# XmasTree.net
KiCad netlist of a schematic drawn in Altium Designer
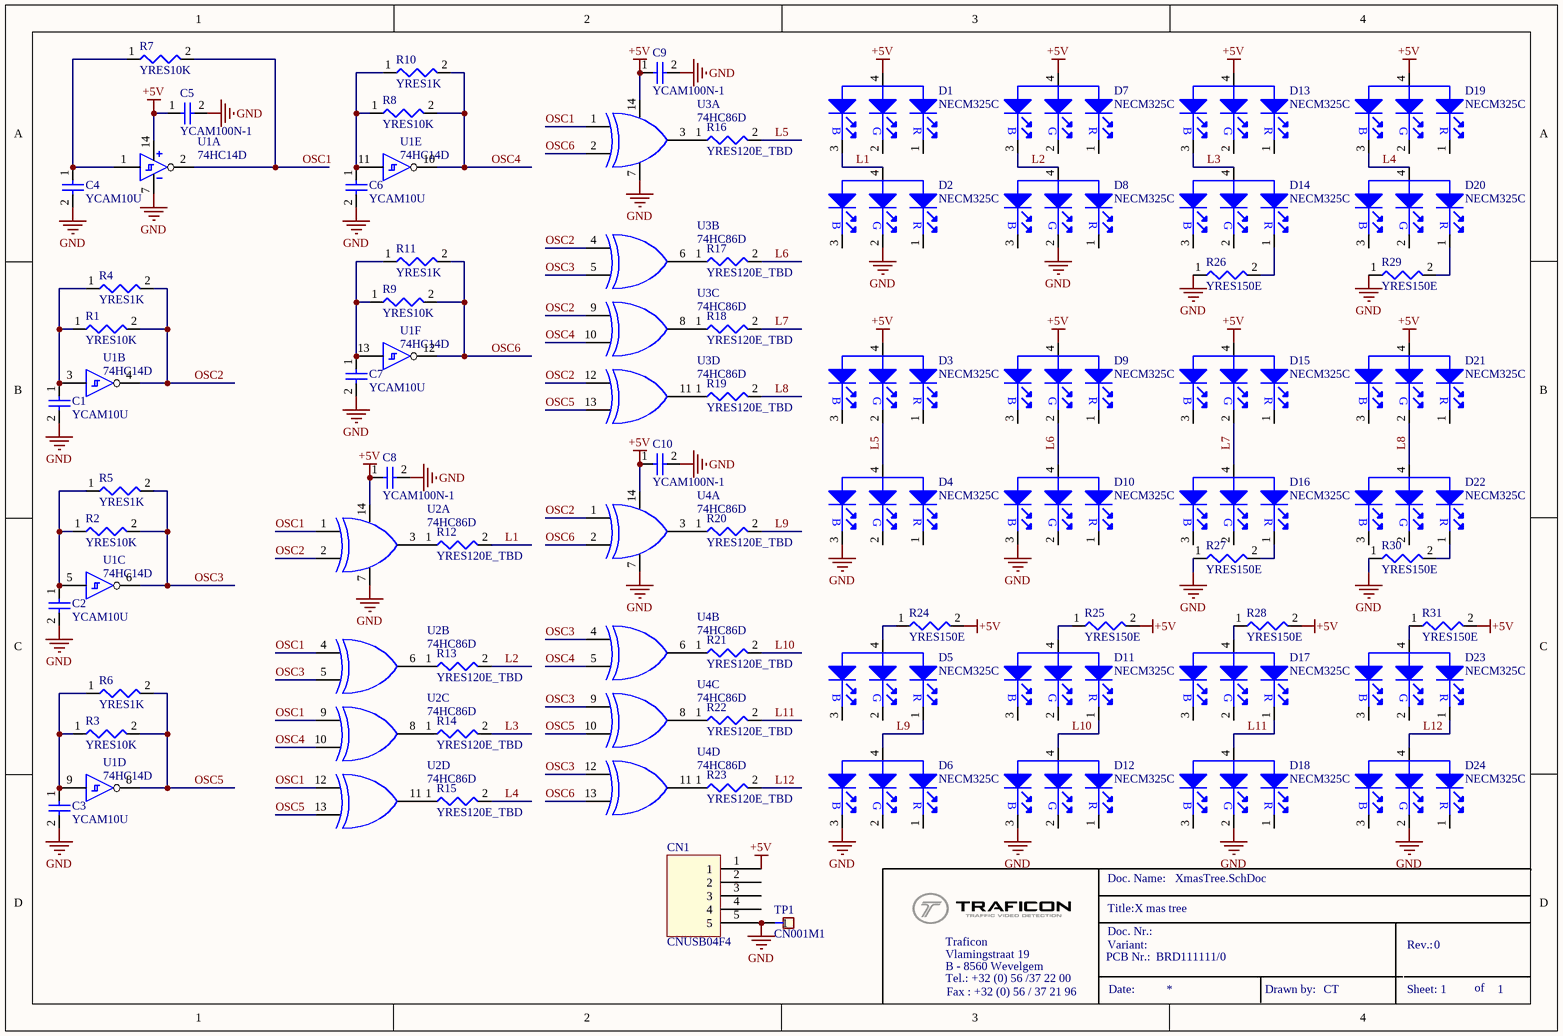
[diagram p0: XmasTree.SchDoc]

(export (version "E")
  (design (tool "Eeschema 10.0.6"))
  (components
    (comp (ref "C1") (value "YCAM10U") (footprint "CA_1206") (libsource (lib "Testing") (part "CA_NONPOL")))
    (comp (ref "C2") (value "YCAM10U") (footprint "CA_1206") (libsource (lib "Testing") (part "CA_NONPOL")))
    (comp (ref "C3") (value "YCAM10U") (footprint "CA_1206") (libsource (lib "Testing") (part "CA_NONPOL")))
    (comp (ref "C4") (value "YCAM10U") (footprint "CA_1206") (libsource (lib "Testing") (part "CA_NONPOL")))
    (comp (ref "C5")
      (value "YCAM100N-1")
      (footprint "CA_0805")
      (libsource (lib "Testing") (part "CA_NONPOL"))
    )
    (comp (ref "C6") (value "YCAM10U") (footprint "CA_1206") (libsource (lib "Testing") (part "CA_NONPOL")))
    (comp (ref "C7") (value "YCAM10U") (footprint "CA_1206") (libsource (lib "Testing") (part "CA_NONPOL")))
    (comp (ref "C8")
      (value "YCAM100N-1")
      (footprint "CA_0805")
      (libsource (lib "Testing") (part "CA_NONPOL"))
    )
    (comp (ref "C9")
      (value "YCAM100N-1")
      (footprint "CA_0805")
      (libsource (lib "Testing") (part "CA_NONPOL"))
    )
    (comp (ref "C10")
      (value "YCAM100N-1")
      (footprint "CA_0805")
      (libsource (lib "Testing") (part "CA_NONPOL"))
    )
    (comp (ref "CN1")
      (value "CNUSB04F4")
      (footprint "CN_USB_AB_mini")
      (fields (field (name "MANUFACTURER") "Multicomp"))
      (libsource (lib "Testing") (part "CN_5P"))
    )
    (comp (ref "D1")
      (value "NECM325C")
      (footprint "DI_PLCC4")
      (fields (field (name "MANUFACTURER") "Nichia"))
      (libsource (lib "Testing") (part "DI_LED_RGB"))
    )
    (comp (ref "D2")
      (value "NECM325C")
      (footprint "DI_PLCC4")
      (fields (field (name "MANUFACTURER") "Nichia"))
      (libsource (lib "Testing") (part "DI_LED_RGB"))
    )
    (comp (ref "D3")
      (value "NECM325C")
      (footprint "DI_PLCC4")
      (fields (field (name "MANUFACTURER") "Nichia"))
      (libsource (lib "Testing") (part "DI_LED_RGB"))
    )
    (comp (ref "D4")
      (value "NECM325C")
      (footprint "DI_PLCC4")
      (fields (field (name "MANUFACTURER") "Nichia"))
      (libsource (lib "Testing") (part "DI_LED_RGB"))
    )
    (comp (ref "D5")
      (value "NECM325C")
      (footprint "DI_PLCC4")
      (fields (field (name "MANUFACTURER") "Nichia"))
      (libsource (lib "Testing") (part "DI_LED_RGB"))
    )
    (comp (ref "D6")
      (value "NECM325C")
      (footprint "DI_PLCC4")
      (fields (field (name "MANUFACTURER") "Nichia"))
      (libsource (lib "Testing") (part "DI_LED_RGB"))
    )
    (comp (ref "D7")
      (value "NECM325C")
      (footprint "DI_PLCC4")
      (fields (field (name "MANUFACTURER") "Nichia"))
      (libsource (lib "Testing") (part "DI_LED_RGB"))
    )
    (comp (ref "D8")
      (value "NECM325C")
      (footprint "DI_PLCC4")
      (fields (field (name "MANUFACTURER") "Nichia"))
      (libsource (lib "Testing") (part "DI_LED_RGB"))
    )
    (comp (ref "D9")
      (value "NECM325C")
      (footprint "DI_PLCC4")
      (fields (field (name "MANUFACTURER") "Nichia"))
      (libsource (lib "Testing") (part "DI_LED_RGB"))
    )
    (comp (ref "D10")
      (value "NECM325C")
      (footprint "DI_PLCC4")
      (fields (field (name "MANUFACTURER") "Nichia"))
      (libsource (lib "Testing") (part "DI_LED_RGB"))
    )
    (comp (ref "D11")
      (value "NECM325C")
      (footprint "DI_PLCC4")
      (fields (field (name "MANUFACTURER") "Nichia"))
      (libsource (lib "Testing") (part "DI_LED_RGB"))
    )
    (comp (ref "D12")
      (value "NECM325C")
      (footprint "DI_PLCC4")
      (fields (field (name "MANUFACTURER") "Nichia"))
      (libsource (lib "Testing") (part "DI_LED_RGB"))
    )
    (comp (ref "D13")
      (value "NECM325C")
      (footprint "DI_PLCC4")
      (fields (field (name "MANUFACTURER") "Nichia"))
      (libsource (lib "Testing") (part "DI_LED_RGB"))
    )
    (comp (ref "D14")
      (value "NECM325C")
      (footprint "DI_PLCC4")
      (fields (field (name "MANUFACTURER") "Nichia"))
      (libsource (lib "Testing") (part "DI_LED_RGB"))
    )
    (comp (ref "D15")
      (value "NECM325C")
      (footprint "DI_PLCC4")
      (fields (field (name "MANUFACTURER") "Nichia"))
      (libsource (lib "Testing") (part "DI_LED_RGB"))
    )
    (comp (ref "D16")
      (value "NECM325C")
      (footprint "DI_PLCC4")
      (fields (field (name "MANUFACTURER") "Nichia"))
      (libsource (lib "Testing") (part "DI_LED_RGB"))
    )
    (comp (ref "D17")
      (value "NECM325C")
      (footprint "DI_PLCC4")
      (fields (field (name "MANUFACTURER") "Nichia"))
      (libsource (lib "Testing") (part "DI_LED_RGB"))
    )
    (comp (ref "D18")
      (value "NECM325C")
      (footprint "DI_PLCC4")
      (fields (field (name "MANUFACTURER") "Nichia"))
      (libsource (lib "Testing") (part "DI_LED_RGB"))
    )
    (comp (ref "D19")
      (value "NECM325C")
      (footprint "DI_PLCC4")
      (fields (field (name "MANUFACTURER") "Nichia"))
      (libsource (lib "Testing") (part "DI_LED_RGB"))
    )
    (comp (ref "D20")
      (value "NECM325C")
      (footprint "DI_PLCC4")
      (fields (field (name "MANUFACTURER") "Nichia"))
      (libsource (lib "Testing") (part "DI_LED_RGB"))
    )
    (comp (ref "D21")
      (value "NECM325C")
      (footprint "DI_PLCC4")
      (fields (field (name "MANUFACTURER") "Nichia"))
      (libsource (lib "Testing") (part "DI_LED_RGB"))
    )
    (comp (ref "D22")
      (value "NECM325C")
      (footprint "DI_PLCC4")
      (fields (field (name "MANUFACTURER") "Nichia"))
      (libsource (lib "Testing") (part "DI_LED_RGB"))
    )
    (comp (ref "D23")
      (value "NECM325C")
      (footprint "DI_PLCC4")
      (fields (field (name "MANUFACTURER") "Nichia"))
      (libsource (lib "Testing") (part "DI_LED_RGB"))
    )
    (comp (ref "D24")
      (value "NECM325C")
      (footprint "DI_PLCC4")
      (fields (field (name "MANUFACTURER") "Nichia"))
      (libsource (lib "Testing") (part "DI_LED_RGB"))
    )
    (comp (ref "R1")
      (value "YRES10K")
      (footprint "RE_1206")
      (description "Resistor")
      (libsource (lib "Testing") (part "RE_RES"))
    )
    (comp (ref "R2")
      (value "YRES10K")
      (footprint "RE_1206")
      (description "Resistor")
      (libsource (lib "Testing") (part "RE_RES"))
    )
    (comp (ref "R3")
      (value "YRES10K")
      (footprint "RE_1206")
      (description "Resistor")
      (libsource (lib "Testing") (part "RE_RES"))
    )
    (comp (ref "R4")
      (value "YRES1K")
      (footprint "RE_1206")
      (description "Resistor")
      (fields (field (name "MANUFACTURER") "Vishay Draloric"))
      (libsource (lib "Testing") (part "RE_RES"))
    )
    (comp (ref "R5")
      (value "YRES1K")
      (footprint "RE_1206")
      (description "Resistor")
      (fields (field (name "MANUFACTURER") "Vishay Draloric"))
      (libsource (lib "Testing") (part "RE_RES"))
    )
    (comp (ref "R6")
      (value "YRES1K")
      (footprint "RE_1206")
      (description "Resistor")
      (fields (field (name "MANUFACTURER") "Vishay Draloric"))
      (libsource (lib "Testing") (part "RE_RES"))
    )
    (comp (ref "R7")
      (value "YRES10K")
      (footprint "RE_1206")
      (description "Resistor")
      (libsource (lib "Testing") (part "RE_RES"))
    )
    (comp (ref "R8")
      (value "YRES10K")
      (footprint "RE_1206")
      (description "Resistor")
      (libsource (lib "Testing") (part "RE_RES"))
    )
    (comp (ref "R9")
      (value "YRES10K")
      (footprint "RE_1206")
      (description "Resistor")
      (libsource (lib "Testing") (part "RE_RES"))
    )
    (comp (ref "R10")
      (value "YRES1K")
      (footprint "RE_1206")
      (description "Resistor")
      (fields (field (name "MANUFACTURER") "Vishay Draloric"))
      (libsource (lib "Testing") (part "RE_RES"))
    )
    (comp (ref "R11")
      (value "YRES1K")
      (footprint "RE_1206")
      (description "Resistor")
      (fields (field (name "MANUFACTURER") "Vishay Draloric"))
      (libsource (lib "Testing") (part "RE_RES"))
    )
    (comp (ref "R12")
      (value "YRES120E_TBD")
      (footprint "RE_1206")
      (description "Resistor")
      (libsource (lib "Testing") (part "RE_RES"))
    )
    (comp (ref "R13")
      (value "YRES120E_TBD")
      (footprint "RE_1206")
      (description "Resistor")
      (libsource (lib "Testing") (part "RE_RES"))
    )
    (comp (ref "R14")
      (value "YRES120E_TBD")
      (footprint "RE_1206")
      (description "Resistor")
      (libsource (lib "Testing") (part "RE_RES"))
    )
    (comp (ref "R15")
      (value "YRES120E_TBD")
      (footprint "RE_1206")
      (description "Resistor")
      (libsource (lib "Testing") (part "RE_RES"))
    )
    (comp (ref "R16")
      (value "YRES120E_TBD")
      (footprint "RE_1206")
      (description "Resistor")
      (libsource (lib "Testing") (part "RE_RES"))
    )
    (comp (ref "R17")
      (value "YRES120E_TBD")
      (footprint "RE_1206")
      (description "Resistor")
      (libsource (lib "Testing") (part "RE_RES"))
    )
    (comp (ref "R18")
      (value "YRES120E_TBD")
      (footprint "RE_1206")
      (description "Resistor")
      (libsource (lib "Testing") (part "RE_RES"))
    )
    (comp (ref "R19")
      (value "YRES120E_TBD")
      (footprint "RE_1206")
      (description "Resistor")
      (libsource (lib "Testing") (part "RE_RES"))
    )
    (comp (ref "R20")
      (value "YRES120E_TBD")
      (footprint "RE_1206")
      (description "Resistor")
      (libsource (lib "Testing") (part "RE_RES"))
    )
    (comp (ref "R21")
      (value "YRES120E_TBD")
      (footprint "RE_1206")
      (description "Resistor")
      (libsource (lib "Testing") (part "RE_RES"))
    )
    (comp (ref "R22")
      (value "YRES120E_TBD")
      (footprint "RE_1206")
      (description "Resistor")
      (libsource (lib "Testing") (part "RE_RES"))
    )
    (comp (ref "R23")
      (value "YRES120E_TBD")
      (footprint "RE_1206")
      (description "Resistor")
      (libsource (lib "Testing") (part "RE_RES"))
    )
    (comp (ref "R24")
      (value "YRES150E")
      (footprint "RE_1206")
      (description "Resistor")
      (libsource (lib "Testing") (part "RE_RES"))
    )
    (comp (ref "R25")
      (value "YRES150E")
      (footprint "RE_1206")
      (description "Resistor")
      (libsource (lib "Testing") (part "RE_RES"))
    )
    (comp (ref "R26")
      (value "YRES150E")
      (footprint "RE_1206")
      (description "Resistor")
      (libsource (lib "Testing") (part "RE_RES"))
    )
    (comp (ref "R27")
      (value "YRES150E")
      (footprint "RE_1206")
      (description "Resistor")
      (libsource (lib "Testing") (part "RE_RES"))
    )
    (comp (ref "R28")
      (value "YRES150E")
      (footprint "RE_1206")
      (description "Resistor")
      (libsource (lib "Testing") (part "RE_RES"))
    )
    (comp (ref "R29")
      (value "YRES150E")
      (footprint "RE_1206")
      (description "Resistor")
      (libsource (lib "Testing") (part "RE_RES"))
    )
    (comp (ref "R30")
      (value "YRES150E")
      (footprint "RE_1206")
      (description "Resistor")
      (libsource (lib "Testing") (part "RE_RES"))
    )
    (comp (ref "R31")
      (value "YRES150E")
      (footprint "RE_1206")
      (description "Resistor")
      (libsource (lib "Testing") (part "RE_RES"))
    )
    (comp (ref "TP1")
      (value "CN001M1")
      (footprint "CN_TP_TH_1.3mm")
      (libsource (lib "Testing") (part "CN_TESTPIN"))
    )
    (comp (ref "U1")
      (value "74HC14D")
      (footprint "SC_SOIC14")
      (fields (field (name "MANUFACTURER") "On Semiconductor"))
      (libsource (lib "Testing") (part "IC_74xx14"))
    )
    (comp (ref "U2")
      (value "74HC86D")
      (footprint "SC_SOIC14")
      (fields (field (name "MANUFACTURER") "NXP"))
      (libsource (lib "Testing") (part "IC_74xx86"))
    )
    (comp (ref "U3")
      (value "74HC86D")
      (footprint "SC_SOIC14")
      (fields (field (name "MANUFACTURER") "NXP"))
      (libsource (lib "Testing") (part "IC_74xx86"))
    )
    (comp (ref "U4")
      (value "74HC86D")
      (footprint "SC_SOIC14")
      (fields (field (name "MANUFACTURER") "NXP"))
      (libsource (lib "Testing") (part "IC_74xx86"))
    )
  )
  (nets
    (net (code "1") (name "+5V") (class "Default")
      (node (ref "C10") (pin "1") (pinfunction "1_1") (pintype "passive"))
      (node (ref "C5") (pin "1") (pinfunction "1_1") (pintype "passive"))
      (node (ref "C8") (pin "1") (pinfunction "1_1") (pintype "passive"))
      (node (ref "C9") (pin "1") (pinfunction "1_1") (pintype "passive"))
      (node (ref "CN1") (pin "1") (pinfunction "1_1") (pintype "passive"))
      (node (ref "D1") (pin "4") (pinfunction "A_4") (pintype "passive"))
      (node (ref "D13") (pin "4") (pinfunction "A_4") (pintype "passive"))
      (node (ref "D15") (pin "4") (pinfunction "A_4") (pintype "passive"))
      (node (ref "D19") (pin "4") (pinfunction "A_4") (pintype "passive"))
      (node (ref "D21") (pin "4") (pinfunction "A_4") (pintype "passive"))
      (node (ref "D3") (pin "4") (pinfunction "A_4") (pintype "passive"))
      (node (ref "D7") (pin "4") (pinfunction "A_4") (pintype "passive"))
      (node (ref "D9") (pin "4") (pinfunction "A_4") (pintype "passive"))
      (node (ref "R24") (pin "2") (pinfunction "2_2") (pintype "passive"))
      (node (ref "R25") (pin "2") (pinfunction "2_2") (pintype "passive"))
      (node (ref "R28") (pin "2") (pinfunction "2_2") (pintype "passive"))
      (node (ref "R31") (pin "2") (pinfunction "2_2") (pintype "passive"))
      (node (ref "U1") (pin "14") (pinfunction "14_14") (pintype "passive"))
      (node (ref "U2") (pin "14") (pinfunction "14_14") (pintype "passive"))
      (node (ref "U3") (pin "14") (pinfunction "14_14") (pintype "passive"))
      (node (ref "U4") (pin "14") (pinfunction "14_14") (pintype "passive"))
    )
    (net (code "2") (name "/L1") (class "Default")
      (node (ref "D1") (pin "3") (pinfunction "C_3") (pintype "passive"))
      (node (ref "D2") (pin "4") (pinfunction "A_4") (pintype "passive"))
      (node (ref "R12") (pin "2") (pinfunction "2_2") (pintype "passive"))
    )
    (net (code "3") (name "/L2") (class "Default")
      (node (ref "D7") (pin "3") (pinfunction "C_3") (pintype "passive"))
      (node (ref "D8") (pin "4") (pinfunction "A_4") (pintype "passive"))
      (node (ref "R13") (pin "2") (pinfunction "2_2") (pintype "passive"))
    )
    (net (code "4") (name "/L3") (class "Default")
      (node (ref "D13") (pin "3") (pinfunction "C_3") (pintype "passive"))
      (node (ref "D14") (pin "4") (pinfunction "A_4") (pintype "passive"))
      (node (ref "R14") (pin "2") (pinfunction "2_2") (pintype "passive"))
    )
    (net (code "5") (name "/L4") (class "Default")
      (node (ref "D19") (pin "3") (pinfunction "C_3") (pintype "passive"))
      (node (ref "D20") (pin "4") (pinfunction "A_4") (pintype "passive"))
      (node (ref "R15") (pin "2") (pinfunction "2_2") (pintype "passive"))
    )
    (net (code "6") (name "/L5") (class "Default")
      (node (ref "D3") (pin "2") (pinfunction "C_2") (pintype "passive"))
      (node (ref "D4") (pin "4") (pinfunction "A_4") (pintype "passive"))
      (node (ref "R16") (pin "2") (pinfunction "2_2") (pintype "passive"))
    )
    (net (code "7") (name "/L6") (class "Default")
      (node (ref "D10") (pin "4") (pinfunction "A_4") (pintype "passive"))
      (node (ref "D9") (pin "2") (pinfunction "C_2") (pintype "passive"))
      (node (ref "R17") (pin "2") (pinfunction "2_2") (pintype "passive"))
    )
    (net (code "8") (name "/L7") (class "Default")
      (node (ref "D15") (pin "2") (pinfunction "C_2") (pintype "passive"))
      (node (ref "D16") (pin "4") (pinfunction "A_4") (pintype "passive"))
      (node (ref "R18") (pin "2") (pinfunction "2_2") (pintype "passive"))
    )
    (net (code "9") (name "/L8") (class "Default")
      (node (ref "D21") (pin "2") (pinfunction "C_2") (pintype "passive"))
      (node (ref "D22") (pin "4") (pinfunction "A_4") (pintype "passive"))
      (node (ref "R19") (pin "2") (pinfunction "2_2") (pintype "passive"))
    )
    (net (code "10") (name "/L9") (class "Default")
      (node (ref "D5") (pin "1") (pinfunction "C_1") (pintype "passive"))
      (node (ref "D6") (pin "4") (pinfunction "A_4") (pintype "passive"))
      (node (ref "R20") (pin "2") (pinfunction "2_2") (pintype "passive"))
    )
    (net (code "11") (name "/L10") (class "Default")
      (node (ref "D11") (pin "1") (pinfunction "C_1") (pintype "passive"))
      (node (ref "D12") (pin "4") (pinfunction "A_4") (pintype "passive"))
      (node (ref "R21") (pin "2") (pinfunction "2_2") (pintype "passive"))
    )
    (net (code "12") (name "/L11") (class "Default")
      (node (ref "D17") (pin "1") (pinfunction "C_1") (pintype "passive"))
      (node (ref "D18") (pin "4") (pinfunction "A_4") (pintype "passive"))
      (node (ref "R22") (pin "2") (pinfunction "2_2") (pintype "passive"))
    )
    (net (code "13") (name "/L12") (class "Default")
      (node (ref "D23") (pin "1") (pinfunction "C_1") (pintype "passive"))
      (node (ref "D24") (pin "4") (pinfunction "A_4") (pintype "passive"))
      (node (ref "R23") (pin "2") (pinfunction "2_2") (pintype "passive"))
    )
    (net (code "14") (name "/OSC1") (class "Default")
      (node (ref "R7") (pin "2") (pinfunction "2_2") (pintype "passive"))
      (node (ref "U1") (pin "2") (pinfunction "2_2") (pintype "passive"))
      (node (ref "U2") (pin "1") (pinfunction "1_1") (pintype "passive"))
      (node (ref "U2") (pin "12") (pinfunction "12_12") (pintype "passive"))
      (node (ref "U2") (pin "4") (pinfunction "4_4") (pintype "passive"))
      (node (ref "U2") (pin "9") (pinfunction "9_9") (pintype "passive"))
      (node (ref "U3") (pin "1") (pinfunction "1_1") (pintype "passive"))
    )
    (net (code "15") (name "/OSC2") (class "Default")
      (node (ref "R1") (pin "2") (pinfunction "2_2") (pintype "passive"))
      (node (ref "R4") (pin "2") (pinfunction "2_2") (pintype "passive"))
      (node (ref "U1") (pin "4") (pinfunction "4_4") (pintype "passive"))
      (node (ref "U2") (pin "2") (pinfunction "2_2") (pintype "passive"))
      (node (ref "U3") (pin "12") (pinfunction "12_12") (pintype "passive"))
      (node (ref "U3") (pin "4") (pinfunction "4_4") (pintype "passive"))
      (node (ref "U3") (pin "9") (pinfunction "9_9") (pintype "passive"))
      (node (ref "U4") (pin "1") (pinfunction "1_1") (pintype "passive"))
    )
    (net (code "16") (name "/OSC3") (class "Default")
      (node (ref "R2") (pin "2") (pinfunction "2_2") (pintype "passive"))
      (node (ref "R5") (pin "2") (pinfunction "2_2") (pintype "passive"))
      (node (ref "U1") (pin "6") (pinfunction "6_6") (pintype "passive"))
      (node (ref "U2") (pin "5") (pinfunction "5_5") (pintype "passive"))
      (node (ref "U3") (pin "5") (pinfunction "5_5") (pintype "passive"))
      (node (ref "U4") (pin "12") (pinfunction "12_12") (pintype "passive"))
      (node (ref "U4") (pin "4") (pinfunction "4_4") (pintype "passive"))
      (node (ref "U4") (pin "9") (pinfunction "9_9") (pintype "passive"))
    )
    (net (code "17") (name "/OSC4") (class "Default")
      (node (ref "R10") (pin "2") (pinfunction "2_2") (pintype "passive"))
      (node (ref "R8") (pin "2") (pinfunction "2_2") (pintype "passive"))
      (node (ref "U1") (pin "10") (pinfunction "10_10") (pintype "passive"))
      (node (ref "U2") (pin "10") (pinfunction "10_10") (pintype "passive"))
      (node (ref "U3") (pin "10") (pinfunction "10_10") (pintype "passive"))
      (node (ref "U4") (pin "5") (pinfunction "5_5") (pintype "passive"))
    )
    (net (code "18") (name "/OSC5") (class "Default")
      (node (ref "R3") (pin "2") (pinfunction "2_2") (pintype "passive"))
      (node (ref "R6") (pin "2") (pinfunction "2_2") (pintype "passive"))
      (node (ref "U1") (pin "8") (pinfunction "8_8") (pintype "passive"))
      (node (ref "U2") (pin "13") (pinfunction "13_13") (pintype "passive"))
      (node (ref "U3") (pin "13") (pinfunction "13_13") (pintype "passive"))
      (node (ref "U4") (pin "10") (pinfunction "10_10") (pintype "passive"))
    )
    (net (code "19") (name "/OSC6") (class "Default")
      (node (ref "R11") (pin "2") (pinfunction "2_2") (pintype "passive"))
      (node (ref "R9") (pin "2") (pinfunction "2_2") (pintype "passive"))
      (node (ref "U1") (pin "12") (pinfunction "12_12") (pintype "passive"))
      (node (ref "U3") (pin "2") (pinfunction "2_2") (pintype "passive"))
      (node (ref "U4") (pin "13") (pinfunction "13_13") (pintype "passive"))
      (node (ref "U4") (pin "2") (pinfunction "2_2") (pintype "passive"))
    )
    (net (code "20") (name "GND") (class "Default")
      (node (ref "C1") (pin "2") (pinfunction "2_2") (pintype "passive"))
      (node (ref "C10") (pin "2") (pinfunction "2_2") (pintype "passive"))
      (node (ref "C2") (pin "2") (pinfunction "2_2") (pintype "passive"))
      (node (ref "C3") (pin "2") (pinfunction "2_2") (pintype "passive"))
      (node (ref "C4") (pin "2") (pinfunction "2_2") (pintype "passive"))
      (node (ref "C5") (pin "2") (pinfunction "2_2") (pintype "passive"))
      (node (ref "C6") (pin "2") (pinfunction "2_2") (pintype "passive"))
      (node (ref "C7") (pin "2") (pinfunction "2_2") (pintype "passive"))
      (node (ref "C8") (pin "2") (pinfunction "2_2") (pintype "passive"))
      (node (ref "C9") (pin "2") (pinfunction "2_2") (pintype "passive"))
      (node (ref "CN1") (pin "5") (pinfunction "5_5") (pintype "passive"))
      (node (ref "D10") (pin "3") (pinfunction "C_3") (pintype "passive"))
      (node (ref "D12") (pin "3") (pinfunction "C_3") (pintype "passive"))
      (node (ref "D18") (pin "2") (pinfunction "C_2") (pintype "passive"))
      (node (ref "D2") (pin "2") (pinfunction "C_2") (pintype "passive"))
      (node (ref "D24") (pin "2") (pinfunction "C_2") (pintype "passive"))
      (node (ref "D4") (pin "3") (pinfunction "C_3") (pintype "passive"))
      (node (ref "D6") (pin "3") (pinfunction "C_3") (pintype "passive"))
      (node (ref "D8") (pin "2") (pinfunction "C_2") (pintype "passive"))
      (node (ref "R26") (pin "1") (pinfunction "1_1") (pintype "passive"))
      (node (ref "R27") (pin "1") (pinfunction "1_1") (pintype "passive"))
      (node (ref "R29") (pin "1") (pinfunction "1_1") (pintype "passive"))
      (node (ref "R30") (pin "1") (pinfunction "1_1") (pintype "passive"))
      (node (ref "TP1") (pin "1") (pinfunction "1_1") (pintype "passive"))
      (node (ref "U1") (pin "7") (pinfunction "7_7") (pintype "passive"))
      (node (ref "U2") (pin "7") (pinfunction "7_7") (pintype "passive"))
      (node (ref "U3") (pin "7") (pinfunction "7_7") (pintype "passive"))
      (node (ref "U4") (pin "7") (pinfunction "7_7") (pintype "passive"))
    )
    (net (code "21") (name "Net-(C1-Pad1)") (class "Default")
      (node (ref "C1") (pin "1") (pinfunction "1_1") (pintype "passive"))
      (node (ref "R1") (pin "1") (pinfunction "1_1") (pintype "passive"))
      (node (ref "R4") (pin "1") (pinfunction "1_1") (pintype "passive"))
      (node (ref "U1") (pin "3") (pinfunction "3_3") (pintype "passive"))
    )
    (net (code "22") (name "Net-(C2-Pad1)") (class "Default")
      (node (ref "C2") (pin "1") (pinfunction "1_1") (pintype "passive"))
      (node (ref "R2") (pin "1") (pinfunction "1_1") (pintype "passive"))
      (node (ref "R5") (pin "1") (pinfunction "1_1") (pintype "passive"))
      (node (ref "U1") (pin "5") (pinfunction "5_5") (pintype "passive"))
    )
    (net (code "23") (name "Net-(C3-Pad1)") (class "Default")
      (node (ref "C3") (pin "1") (pinfunction "1_1") (pintype "passive"))
      (node (ref "R3") (pin "1") (pinfunction "1_1") (pintype "passive"))
      (node (ref "R6") (pin "1") (pinfunction "1_1") (pintype "passive"))
      (node (ref "U1") (pin "9") (pinfunction "9_9") (pintype "passive"))
    )
    (net (code "24") (name "Net-(C4-Pad1)") (class "Default")
      (node (ref "C4") (pin "1") (pinfunction "1_1") (pintype "passive"))
      (node (ref "R7") (pin "1") (pinfunction "1_1") (pintype "passive"))
      (node (ref "U1") (pin "1") (pinfunction "1_1") (pintype "passive"))
    )
    (net (code "25") (name "Net-(C6-Pad1)") (class "Default")
      (node (ref "C6") (pin "1") (pinfunction "1_1") (pintype "passive"))
      (node (ref "R10") (pin "1") (pinfunction "1_1") (pintype "passive"))
      (node (ref "R8") (pin "1") (pinfunction "1_1") (pintype "passive"))
      (node (ref "U1") (pin "11") (pinfunction "11_11") (pintype "passive"))
    )
    (net (code "26") (name "Net-(C7-Pad1)") (class "Default")
      (node (ref "C7") (pin "1") (pinfunction "1_1") (pintype "passive"))
      (node (ref "R11") (pin "1") (pinfunction "1_1") (pintype "passive"))
      (node (ref "R9") (pin "1") (pinfunction "1_1") (pintype "passive"))
      (node (ref "U1") (pin "13") (pinfunction "13_13") (pintype "passive"))
    )
    (net (code "27") (name "Net-(D5-A)") (class "Default")
      (node (ref "D5") (pin "4") (pinfunction "A_4") (pintype "passive"))
      (node (ref "R24") (pin "1") (pinfunction "1_1") (pintype "passive"))
    )
    (net (code "28") (name "Net-(D11-A)") (class "Default")
      (node (ref "D11") (pin "4") (pinfunction "A_4") (pintype "passive"))
      (node (ref "R25") (pin "1") (pinfunction "1_1") (pintype "passive"))
    )
    (net (code "29") (name "Net-(D14-C-Pad1)") (class "Default")
      (node (ref "D14") (pin "1") (pinfunction "C_1") (pintype "passive"))
      (node (ref "R26") (pin "2") (pinfunction "2_2") (pintype "passive"))
    )
    (net (code "30") (name "Net-(D16-C-Pad1)") (class "Default")
      (node (ref "D16") (pin "1") (pinfunction "C_1") (pintype "passive"))
      (node (ref "R27") (pin "2") (pinfunction "2_2") (pintype "passive"))
    )
    (net (code "31") (name "Net-(D17-A)") (class "Default")
      (node (ref "D17") (pin "4") (pinfunction "A_4") (pintype "passive"))
      (node (ref "R28") (pin "1") (pinfunction "1_1") (pintype "passive"))
    )
    (net (code "32") (name "Net-(D20-C-Pad1)") (class "Default")
      (node (ref "D20") (pin "1") (pinfunction "C_1") (pintype "passive"))
      (node (ref "R29") (pin "2") (pinfunction "2_2") (pintype "passive"))
    )
    (net (code "33") (name "Net-(D22-C-Pad1)") (class "Default")
      (node (ref "D22") (pin "1") (pinfunction "C_1") (pintype "passive"))
      (node (ref "R30") (pin "2") (pinfunction "2_2") (pintype "passive"))
    )
    (net (code "34") (name "Net-(D23-A)") (class "Default")
      (node (ref "D23") (pin "4") (pinfunction "A_4") (pintype "passive"))
      (node (ref "R31") (pin "1") (pinfunction "1_1") (pintype "passive"))
    )
    (net (code "35") (name "Net-(R12-Pad1)") (class "Default")
      (node (ref "R12") (pin "1") (pinfunction "1_1") (pintype "passive"))
      (node (ref "U2") (pin "3") (pinfunction "3_3") (pintype "passive"))
    )
    (net (code "36") (name "Net-(R13-Pad1)") (class "Default")
      (node (ref "R13") (pin "1") (pinfunction "1_1") (pintype "passive"))
      (node (ref "U2") (pin "6") (pinfunction "6_6") (pintype "passive"))
    )
    (net (code "37") (name "Net-(R14-Pad1)") (class "Default")
      (node (ref "R14") (pin "1") (pinfunction "1_1") (pintype "passive"))
      (node (ref "U2") (pin "8") (pinfunction "8_8") (pintype "passive"))
    )
    (net (code "38") (name "Net-(R15-Pad1)") (class "Default")
      (node (ref "R15") (pin "1") (pinfunction "1_1") (pintype "passive"))
      (node (ref "U2") (pin "11") (pinfunction "11_11") (pintype "passive"))
    )
    (net (code "39") (name "Net-(R16-Pad1)") (class "Default")
      (node (ref "R16") (pin "1") (pinfunction "1_1") (pintype "passive"))
      (node (ref "U3") (pin "3") (pinfunction "3_3") (pintype "passive"))
    )
    (net (code "40") (name "Net-(R17-Pad1)") (class "Default")
      (node (ref "R17") (pin "1") (pinfunction "1_1") (pintype "passive"))
      (node (ref "U3") (pin "6") (pinfunction "6_6") (pintype "passive"))
    )
    (net (code "41") (name "Net-(R18-Pad1)") (class "Default")
      (node (ref "R18") (pin "1") (pinfunction "1_1") (pintype "passive"))
      (node (ref "U3") (pin "8") (pinfunction "8_8") (pintype "passive"))
    )
    (net (code "42") (name "Net-(R19-Pad1)") (class "Default")
      (node (ref "R19") (pin "1") (pinfunction "1_1") (pintype "passive"))
      (node (ref "U3") (pin "11") (pinfunction "11_11") (pintype "passive"))
    )
    (net (code "43") (name "Net-(R20-Pad1)") (class "Default")
      (node (ref "R20") (pin "1") (pinfunction "1_1") (pintype "passive"))
      (node (ref "U4") (pin "3") (pinfunction "3_3") (pintype "passive"))
    )
    (net (code "44") (name "Net-(R21-Pad1)") (class "Default")
      (node (ref "R21") (pin "1") (pinfunction "1_1") (pintype "passive"))
      (node (ref "U4") (pin "6") (pinfunction "6_6") (pintype "passive"))
    )
    (net (code "45") (name "Net-(R22-Pad1)") (class "Default")
      (node (ref "R22") (pin "1") (pinfunction "1_1") (pintype "passive"))
      (node (ref "U4") (pin "8") (pinfunction "8_8") (pintype "passive"))
    )
    (net (code "46") (name "Net-(R23-Pad1)") (class "Default")
      (node (ref "R23") (pin "1") (pinfunction "1_1") (pintype "passive"))
      (node (ref "U4") (pin "11") (pinfunction "11_11") (pintype "passive"))
    )
    (net (code "47") (name "unconnected-(CN1-Pad2)") (class "Default")
      (node (ref "CN1") (pin "2") (pinfunction "2_2") (pintype "passive"))
    )
    (net (code "48") (name "unconnected-(CN1-Pad3)") (class "Default")
      (node (ref "CN1") (pin "3") (pinfunction "3_3") (pintype "passive"))
    )
    (net (code "49") (name "unconnected-(CN1-Pad4)") (class "Default")
      (node (ref "CN1") (pin "4") (pinfunction "4_4") (pintype "passive"))
    )
    (net (code "50") (name "unconnected-(D1-C-Pad1)") (class "Default")
      (node (ref "D1") (pin "1") (pinfunction "C_1") (pintype "passive"))
    )
    (net (code "51") (name "unconnected-(D1-C-Pad2)") (class "Default")
      (node (ref "D1") (pin "2") (pinfunction "C_2") (pintype "passive"))
    )
    (net (code "52") (name "unconnected-(D2-C-Pad1)") (class "Default")
      (node (ref "D2") (pin "1") (pinfunction "C_1") (pintype "passive"))
    )
    (net (code "53") (name "unconnected-(D2-C-Pad3)") (class "Default")
      (node (ref "D2") (pin "3") (pinfunction "C_3") (pintype "passive"))
    )
    (net (code "54") (name "unconnected-(D3-C-Pad1)") (class "Default")
      (node (ref "D3") (pin "1") (pinfunction "C_1") (pintype "passive"))
    )
    (net (code "55") (name "unconnected-(D3-C-Pad3)") (class "Default")
      (node (ref "D3") (pin "3") (pinfunction "C_3") (pintype "passive"))
    )
    (net (code "56") (name "unconnected-(D4-C-Pad1)") (class "Default")
      (node (ref "D4") (pin "1") (pinfunction "C_1") (pintype "passive"))
    )
    (net (code "57") (name "unconnected-(D4-C-Pad2)") (class "Default")
      (node (ref "D4") (pin "2") (pinfunction "C_2") (pintype "passive"))
    )
    (net (code "58") (name "unconnected-(D5-C-Pad2)") (class "Default")
      (node (ref "D5") (pin "2") (pinfunction "C_2") (pintype "passive"))
    )
    (net (code "59") (name "unconnected-(D5-C-Pad3)") (class "Default")
      (node (ref "D5") (pin "3") (pinfunction "C_3") (pintype "passive"))
    )
    (net (code "60") (name "unconnected-(D6-C-Pad1)") (class "Default")
      (node (ref "D6") (pin "1") (pinfunction "C_1") (pintype "passive"))
    )
    (net (code "61") (name "unconnected-(D6-C-Pad2)") (class "Default")
      (node (ref "D6") (pin "2") (pinfunction "C_2") (pintype "passive"))
    )
    (net (code "62") (name "unconnected-(D7-C-Pad1)") (class "Default")
      (node (ref "D7") (pin "1") (pinfunction "C_1") (pintype "passive"))
    )
    (net (code "63") (name "unconnected-(D7-C-Pad2)") (class "Default")
      (node (ref "D7") (pin "2") (pinfunction "C_2") (pintype "passive"))
    )
    (net (code "64") (name "unconnected-(D8-C-Pad1)") (class "Default")
      (node (ref "D8") (pin "1") (pinfunction "C_1") (pintype "passive"))
    )
    (net (code "65") (name "unconnected-(D8-C-Pad3)") (class "Default")
      (node (ref "D8") (pin "3") (pinfunction "C_3") (pintype "passive"))
    )
    (net (code "66") (name "unconnected-(D9-C-Pad1)") (class "Default")
      (node (ref "D9") (pin "1") (pinfunction "C_1") (pintype "passive"))
    )
    (net (code "67") (name "unconnected-(D9-C-Pad3)") (class "Default")
      (node (ref "D9") (pin "3") (pinfunction "C_3") (pintype "passive"))
    )
    (net (code "68") (name "unconnected-(D10-C-Pad1)") (class "Default")
      (node (ref "D10") (pin "1") (pinfunction "C_1") (pintype "passive"))
    )
    (net (code "69") (name "unconnected-(D10-C-Pad2)") (class "Default")
      (node (ref "D10") (pin "2") (pinfunction "C_2") (pintype "passive"))
    )
    (net (code "70") (name "unconnected-(D11-C-Pad2)") (class "Default")
      (node (ref "D11") (pin "2") (pinfunction "C_2") (pintype "passive"))
    )
    (net (code "71") (name "unconnected-(D11-C-Pad3)") (class "Default")
      (node (ref "D11") (pin "3") (pinfunction "C_3") (pintype "passive"))
    )
    (net (code "72") (name "unconnected-(D12-C-Pad1)") (class "Default")
      (node (ref "D12") (pin "1") (pinfunction "C_1") (pintype "passive"))
    )
    (net (code "73") (name "unconnected-(D12-C-Pad2)") (class "Default")
      (node (ref "D12") (pin "2") (pinfunction "C_2") (pintype "passive"))
    )
    (net (code "74") (name "unconnected-(D13-C-Pad1)") (class "Default")
      (node (ref "D13") (pin "1") (pinfunction "C_1") (pintype "passive"))
    )
    (net (code "75") (name "unconnected-(D13-C-Pad2)") (class "Default")
      (node (ref "D13") (pin "2") (pinfunction "C_2") (pintype "passive"))
    )
    (net (code "76") (name "unconnected-(D14-C-Pad2)") (class "Default")
      (node (ref "D14") (pin "2") (pinfunction "C_2") (pintype "passive"))
    )
    (net (code "77") (name "unconnected-(D14-C-Pad3)") (class "Default")
      (node (ref "D14") (pin "3") (pinfunction "C_3") (pintype "passive"))
    )
    (net (code "78") (name "unconnected-(D15-C-Pad1)") (class "Default")
      (node (ref "D15") (pin "1") (pinfunction "C_1") (pintype "passive"))
    )
    (net (code "79") (name "unconnected-(D15-C-Pad3)") (class "Default")
      (node (ref "D15") (pin "3") (pinfunction "C_3") (pintype "passive"))
    )
    (net (code "80") (name "unconnected-(D16-C-Pad2)") (class "Default")
      (node (ref "D16") (pin "2") (pinfunction "C_2") (pintype "passive"))
    )
    (net (code "81") (name "unconnected-(D16-C-Pad3)") (class "Default")
      (node (ref "D16") (pin "3") (pinfunction "C_3") (pintype "passive"))
    )
    (net (code "82") (name "unconnected-(D17-C-Pad2)") (class "Default")
      (node (ref "D17") (pin "2") (pinfunction "C_2") (pintype "passive"))
    )
    (net (code "83") (name "unconnected-(D17-C-Pad3)") (class "Default")
      (node (ref "D17") (pin "3") (pinfunction "C_3") (pintype "passive"))
    )
    (net (code "84") (name "unconnected-(D18-C-Pad1)") (class "Default")
      (node (ref "D18") (pin "1") (pinfunction "C_1") (pintype "passive"))
    )
    (net (code "85") (name "unconnected-(D18-C-Pad3)") (class "Default")
      (node (ref "D18") (pin "3") (pinfunction "C_3") (pintype "passive"))
    )
    (net (code "86") (name "unconnected-(D19-C-Pad1)") (class "Default")
      (node (ref "D19") (pin "1") (pinfunction "C_1") (pintype "passive"))
    )
    (net (code "87") (name "unconnected-(D19-C-Pad2)") (class "Default")
      (node (ref "D19") (pin "2") (pinfunction "C_2") (pintype "passive"))
    )
    (net (code "88") (name "unconnected-(D20-C-Pad2)") (class "Default")
      (node (ref "D20") (pin "2") (pinfunction "C_2") (pintype "passive"))
    )
    (net (code "89") (name "unconnected-(D20-C-Pad3)") (class "Default")
      (node (ref "D20") (pin "3") (pinfunction "C_3") (pintype "passive"))
    )
    (net (code "90") (name "unconnected-(D21-C-Pad1)") (class "Default")
      (node (ref "D21") (pin "1") (pinfunction "C_1") (pintype "passive"))
    )
    (net (code "91") (name "unconnected-(D21-C-Pad3)") (class "Default")
      (node (ref "D21") (pin "3") (pinfunction "C_3") (pintype "passive"))
    )
    (net (code "92") (name "unconnected-(D22-C-Pad2)") (class "Default")
      (node (ref "D22") (pin "2") (pinfunction "C_2") (pintype "passive"))
    )
    (net (code "93") (name "unconnected-(D22-C-Pad3)") (class "Default")
      (node (ref "D22") (pin "3") (pinfunction "C_3") (pintype "passive"))
    )
    (net (code "94") (name "unconnected-(D23-C-Pad2)") (class "Default")
      (node (ref "D23") (pin "2") (pinfunction "C_2") (pintype "passive"))
    )
    (net (code "95") (name "unconnected-(D23-C-Pad3)") (class "Default")
      (node (ref "D23") (pin "3") (pinfunction "C_3") (pintype "passive"))
    )
    (net (code "96") (name "unconnected-(D24-C-Pad1)") (class "Default")
      (node (ref "D24") (pin "1") (pinfunction "C_1") (pintype "passive"))
    )
    (net (code "97") (name "unconnected-(D24-C-Pad3)") (class "Default")
      (node (ref "D24") (pin "3") (pinfunction "C_3") (pintype "passive"))
    )
  )
)
